# Sheet.net
KiCad netlist of a schematic drawn in Altium Designer
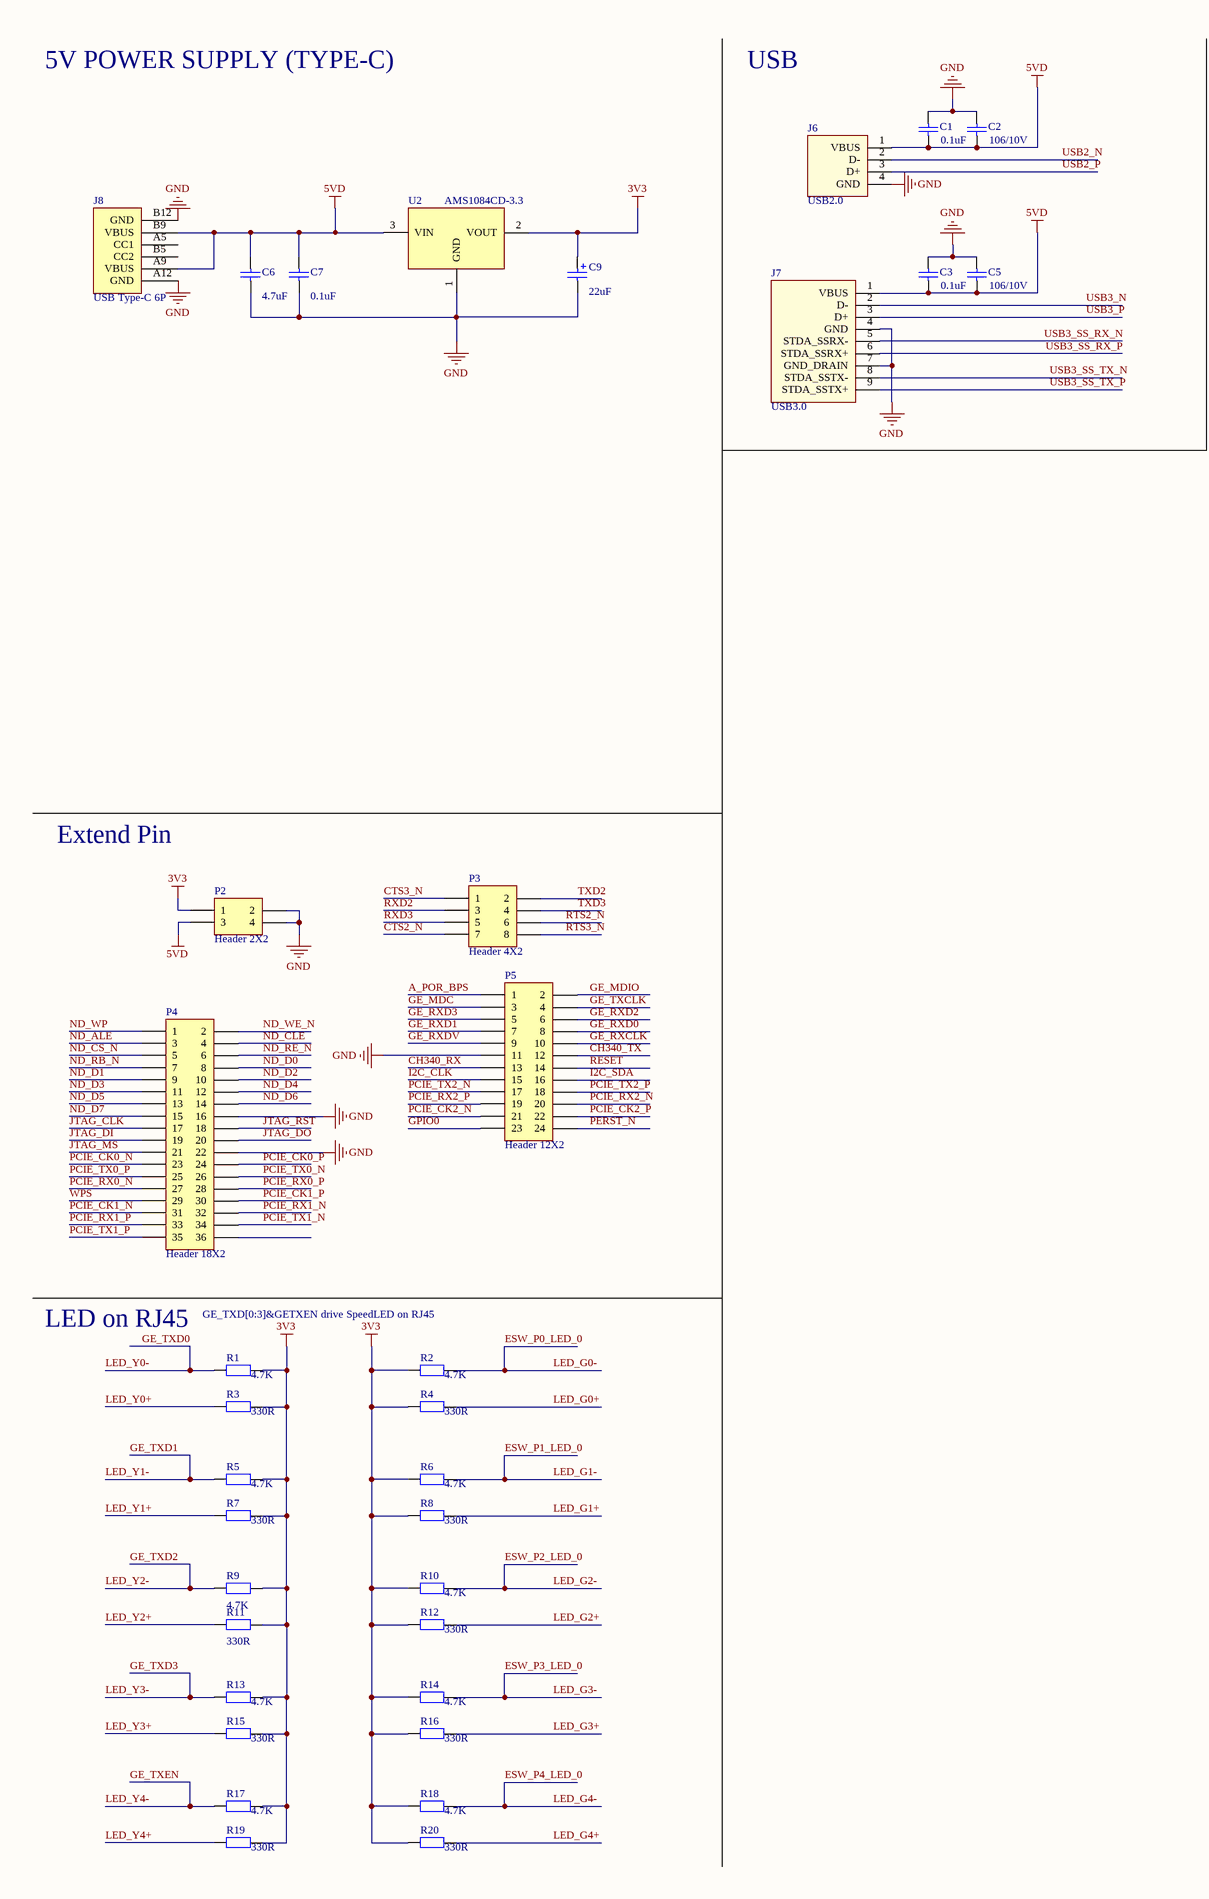
[diagram p0: Sheet.SchDoc, left]
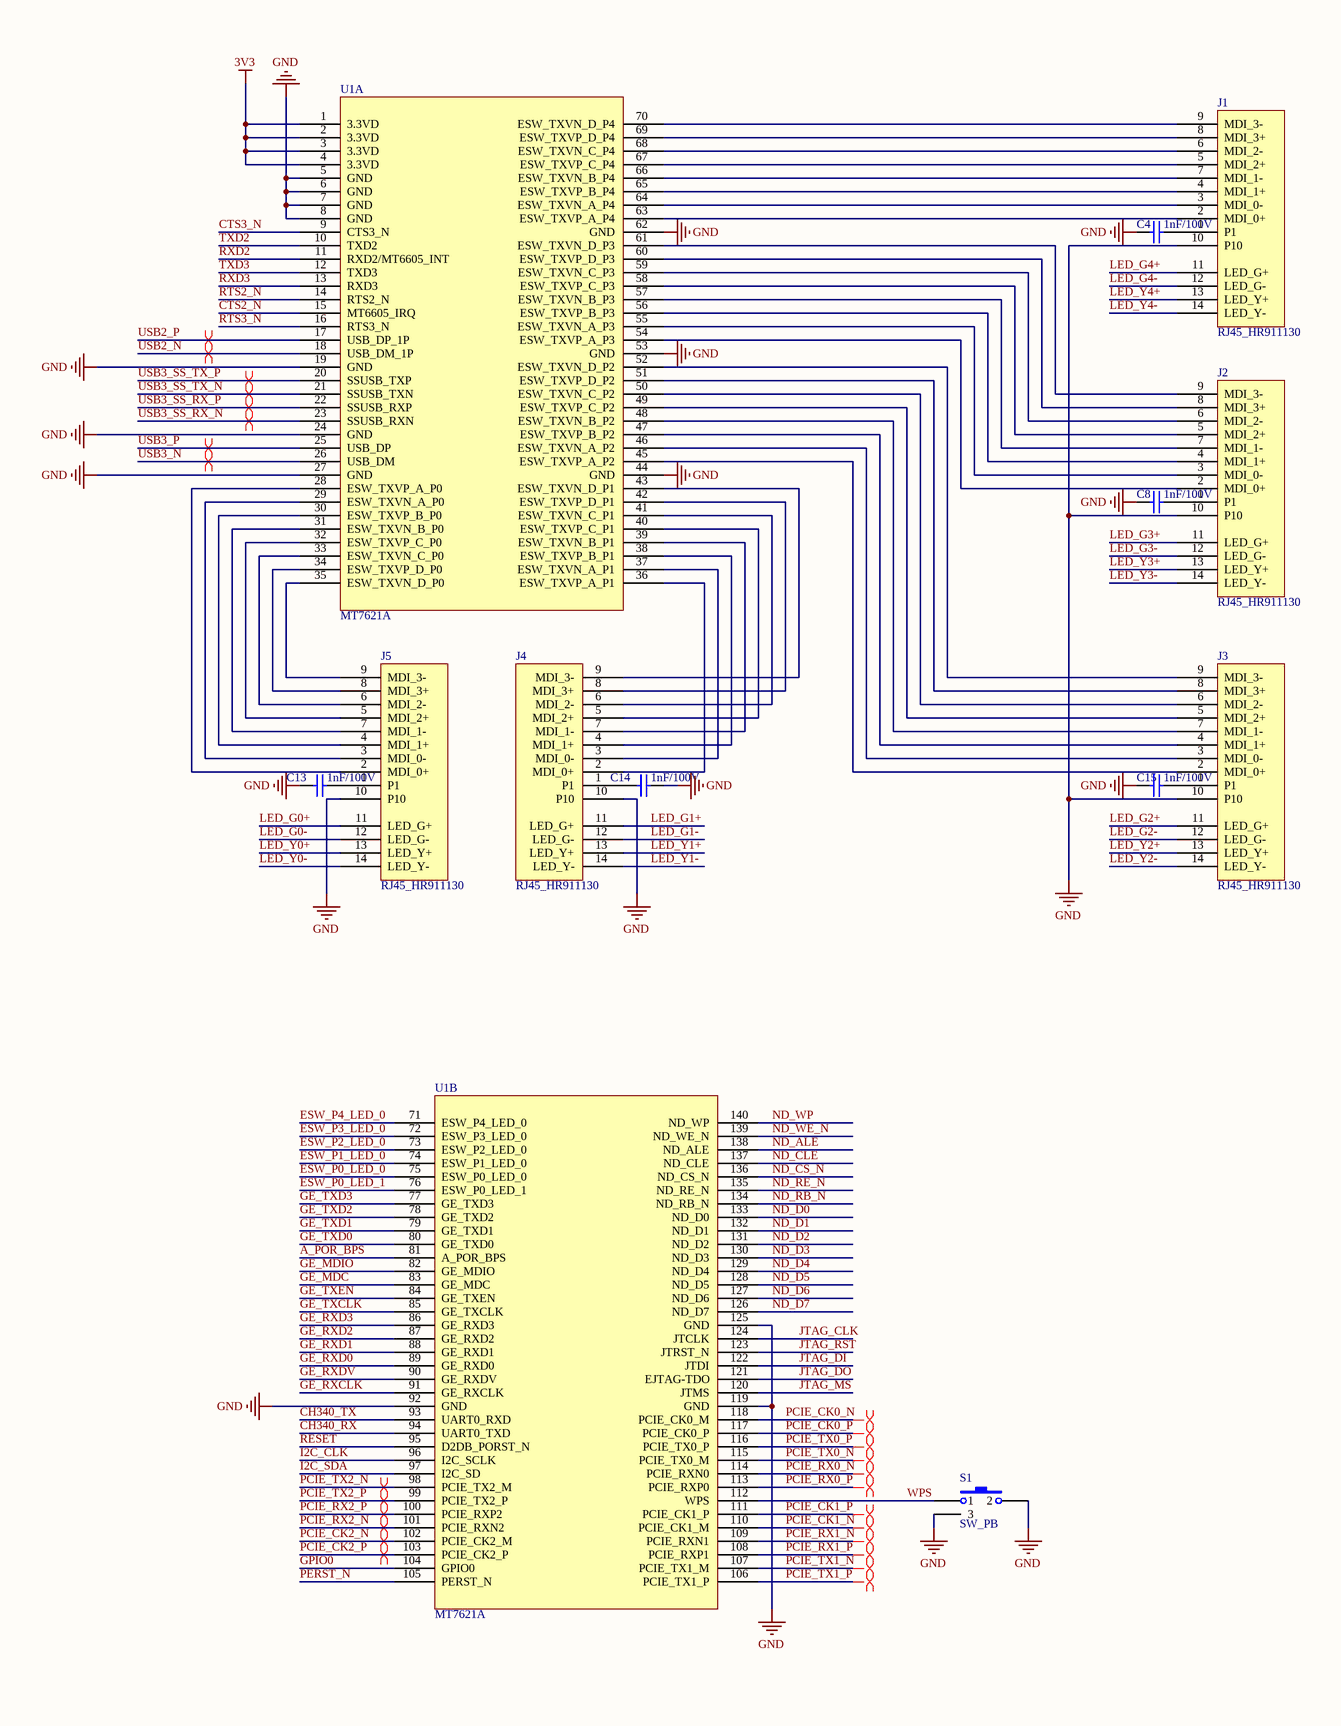
[diagram p1: Sheet.SchDoc, right]

(export (version "E")
  (design (tool "Eeschema 10.0.6"))
  (components
    (comp (ref "C1")
      (value "0.1uF")
      (footprint "6-0805")
      (description "Capacitor")
      (fields (field (name "Comment") "Cap") (field (name "PUBLISHER") "Altium Limited"))
      (libsource (lib "Miscellaneous Devices") (part "Cap"))
    )
    (comp (ref "C2")
      (value "106/10V")
      (footprint "6-0805")
      (description "Capacitor")
      (fields (field (name "Comment") "Cap") (field (name "PUBLISHER") "Altium Limited"))
      (libsource (lib "Miscellaneous Devices") (part "Cap"))
    )
    (comp (ref "C3")
      (value "0.1uF")
      (footprint "6-0805")
      (description "Capacitor")
      (fields (field (name "Comment") "Cap") (field (name "PUBLISHER") "Altium Limited"))
      (libsource (lib "Miscellaneous Devices") (part "Cap"))
    )
    (comp (ref "C4")
      (value "1nF/100V")
      (footprint "6-0805")
      (description "Capacitor")
      (fields (field (name "Comment") "Cap") (field (name "PUBLISHER") "Altium Limited"))
      (libsource (lib "Miscellaneous Devices") (part "Cap"))
    )
    (comp (ref "C5")
      (value "106/10V")
      (footprint "6-0805")
      (description "Capacitor")
      (fields (field (name "Comment") "Cap") (field (name "PUBLISHER") "Altium Limited"))
      (libsource (lib "Miscellaneous Devices") (part "Cap"))
    )
    (comp (ref "C6")
      (value "4.7uF")
      (footprint "6-0805")
      (description "Capacitor")
      (fields (field (name "Comment") "Cap") (field (name "PUBLISHER") "Altium Limited"))
      (libsource (lib "Miscellaneous Devices") (part "Cap"))
    )
    (comp (ref "C7")
      (value "0.1uF")
      (footprint "6-0805")
      (description "Capacitor")
      (fields (field (name "Comment") "Cap") (field (name "PUBLISHER") "Altium Limited"))
      (libsource (lib "Miscellaneous Devices") (part "Cap"))
    )
    (comp (ref "C8")
      (value "1nF/100V")
      (footprint "6-0805")
      (description "Capacitor")
      (fields (field (name "Comment") "Cap") (field (name "PUBLISHER") "Altium Limited"))
      (libsource (lib "Miscellaneous Devices") (part "Cap"))
    )
    (comp (ref "C9")
      (value "22uF")
      (footprint "3528B")
      (description "Polarized Capacitor (Axial)")
      (fields (field (name "Comment") "Cap Pol2") (field (name "PUBLISHER") "Altium Limited"))
      (libsource (lib "Miscellaneous Devices") (part "Cap Pol2"))
    )
    (comp (ref "C13")
      (value "1nF/100V")
      (footprint "6-0805")
      (description "Capacitor")
      (fields (field (name "Comment") "Cap") (field (name "PUBLISHER") "Altium Limited"))
      (libsource (lib "Miscellaneous Devices") (part "Cap"))
    )
    (comp (ref "C14")
      (value "1nF/100V")
      (footprint "6-0805")
      (description "Capacitor")
      (fields (field (name "Comment") "Cap") (field (name "PUBLISHER") "Altium Limited"))
      (libsource (lib "Miscellaneous Devices") (part "Cap"))
    )
    (comp (ref "C15")
      (value "1nF/100V")
      (footprint "6-0805")
      (description "Capacitor")
      (fields (field (name "Comment") "Cap") (field (name "PUBLISHER") "Altium Limited"))
      (libsource (lib "Miscellaneous Devices") (part "Cap"))
    )
    (comp (ref "J1")
      (value "RJ45_HR911130")
      (footprint "RJ45_HR911130")
      (libsource (lib "7621_cmp") (part "RJ45_HR911130"))
    )
    (comp (ref "J2")
      (value "RJ45_HR911130")
      (footprint "RJ45_HR911130")
      (libsource (lib "7621_cmp") (part "RJ45_HR911130"))
    )
    (comp (ref "J3")
      (value "RJ45_HR911130")
      (footprint "RJ45_HR911130")
      (libsource (lib "7621_cmp") (part "RJ45_HR911130"))
    )
    (comp (ref "J4")
      (value "RJ45_HR911130")
      (footprint "RJ45_HR911130")
      (libsource (lib "") (part "RJ45_HR911130_1"))
    )
    (comp (ref "J5")
      (value "RJ45_HR911130")
      (footprint "RJ45_HR911130")
      (libsource (lib "7621_cmp") (part "RJ45_HR911130"))
    )
    (comp (ref "J6") (value "USB2.0") (footprint "USB2.0") (libsource (lib "7621_cmp") (part "USB2.0")))
    (comp (ref "J7") (value "USB3.0") (footprint "USB3.0_0") (libsource (lib "7621_cmp") (part "USB3.0")))
    (comp (ref "J8")
      (value "USB Type-C 6P")
      (footprint "USB Type-C 6P")
      (libsource (lib "7621_cmp") (part "USB Type-C 6P"))
    )
    (comp (ref "P2")
      (value "Header 2X2")
      (footprint "HDR2X2")
      (description "Header, 2-Pin, Dual row")
      (fields (field (name "PUBLISHER") "Altium Limited"))
      (libsource (lib "Miscellaneous Connectors") (part "Header 2X2"))
    )
    (comp (ref "P3")
      (value "Header 4X2")
      (footprint "HDR2X4")
      (description "Header, 4-Pin, Dual row")
      (fields (field (name "PUBLISHER") "Altium Limited"))
      (libsource (lib "Miscellaneous Connectors") (part "Header 4X2"))
    )
    (comp (ref "P4")
      (value "Header 18X2")
      (footprint "HDR2X18")
      (description "Header, 18-Pin, Dual row")
      (fields (field (name "PUBLISHER") "Altium Limited"))
      (libsource (lib "Miscellaneous Connectors") (part "Header 18X2"))
    )
    (comp (ref "P5")
      (value "Header 12X2")
      (footprint "HDR2X12")
      (description "Header, 12-Pin, Dual row")
      (fields (field (name "PUBLISHER") "Altium Limited"))
      (libsource (lib "Miscellaneous Connectors") (part "Header 12X2"))
    )
    (comp (ref "R1")
      (value "4.7K")
      (footprint "6-0805")
      (description "Resistor")
      (fields (field (name "Comment") "Res2") (field (name "PUBLISHER") "Altium Limited"))
      (libsource (lib "Miscellaneous Devices") (part "Res2"))
    )
    (comp (ref "R2")
      (value "4.7K")
      (footprint "6-0805")
      (description "Resistor")
      (fields (field (name "Comment") "Res2") (field (name "PUBLISHER") "Altium Limited"))
      (libsource (lib "Miscellaneous Devices") (part "Res2"))
    )
    (comp (ref "R3")
      (value "330R")
      (footprint "6-0805")
      (description "Resistor")
      (fields (field (name "Comment") "Res2") (field (name "PUBLISHER") "Altium Limited"))
      (libsource (lib "Miscellaneous Devices") (part "Res2"))
    )
    (comp (ref "R4")
      (value "330R")
      (footprint "6-0805")
      (description "Resistor")
      (fields (field (name "Comment") "Res2") (field (name "PUBLISHER") "Altium Limited"))
      (libsource (lib "Miscellaneous Devices") (part "Res2"))
    )
    (comp (ref "R5")
      (value "4.7K")
      (footprint "6-0805")
      (description "Resistor")
      (fields (field (name "Comment") "Res2") (field (name "PUBLISHER") "Altium Limited"))
      (libsource (lib "Miscellaneous Devices") (part "Res2"))
    )
    (comp (ref "R6")
      (value "4.7K")
      (footprint "6-0805")
      (description "Resistor")
      (fields (field (name "Comment") "Res2") (field (name "PUBLISHER") "Altium Limited"))
      (libsource (lib "Miscellaneous Devices") (part "Res2"))
    )
    (comp (ref "R7")
      (value "330R")
      (footprint "6-0805")
      (description "Resistor")
      (fields (field (name "Comment") "Res2") (field (name "PUBLISHER") "Altium Limited"))
      (libsource (lib "Miscellaneous Devices") (part "Res2"))
    )
    (comp (ref "R8")
      (value "330R")
      (footprint "6-0805")
      (description "Resistor")
      (fields (field (name "Comment") "Res2") (field (name "PUBLISHER") "Altium Limited"))
      (libsource (lib "Miscellaneous Devices") (part "Res2"))
    )
    (comp (ref "R9")
      (value "4.7K")
      (footprint "6-0805")
      (description "Resistor")
      (fields (field (name "Comment") "Res2") (field (name "PUBLISHER") "Altium Limited"))
      (libsource (lib "Miscellaneous Devices") (part "Res2"))
    )
    (comp (ref "R10")
      (value "4.7K")
      (footprint "6-0805")
      (description "Resistor")
      (fields (field (name "Comment") "Res2") (field (name "PUBLISHER") "Altium Limited"))
      (libsource (lib "Miscellaneous Devices") (part "Res2"))
    )
    (comp (ref "R11")
      (value "330R")
      (footprint "6-0805")
      (description "Resistor")
      (fields (field (name "Comment") "Res2") (field (name "PUBLISHER") "Altium Limited"))
      (libsource (lib "Miscellaneous Devices") (part "Res2"))
    )
    (comp (ref "R12")
      (value "330R")
      (footprint "6-0805")
      (description "Resistor")
      (fields (field (name "Comment") "Res2") (field (name "PUBLISHER") "Altium Limited"))
      (libsource (lib "Miscellaneous Devices") (part "Res2"))
    )
    (comp (ref "R13")
      (value "4.7K")
      (footprint "6-0805")
      (description "Resistor")
      (fields (field (name "Comment") "Res2") (field (name "PUBLISHER") "Altium Limited"))
      (libsource (lib "Miscellaneous Devices") (part "Res2"))
    )
    (comp (ref "R14")
      (value "4.7K")
      (footprint "6-0805")
      (description "Resistor")
      (fields (field (name "Comment") "Res2") (field (name "PUBLISHER") "Altium Limited"))
      (libsource (lib "Miscellaneous Devices") (part "Res2"))
    )
    (comp (ref "R15")
      (value "330R")
      (footprint "6-0805")
      (description "Resistor")
      (fields (field (name "Comment") "Res2") (field (name "PUBLISHER") "Altium Limited"))
      (libsource (lib "Miscellaneous Devices") (part "Res2"))
    )
    (comp (ref "R16")
      (value "330R")
      (footprint "6-0805")
      (description "Resistor")
      (fields (field (name "Comment") "Res2") (field (name "PUBLISHER") "Altium Limited"))
      (libsource (lib "Miscellaneous Devices") (part "Res2"))
    )
    (comp (ref "R17")
      (value "4.7K")
      (footprint "6-0805")
      (description "Resistor")
      (fields (field (name "Comment") "Res2") (field (name "PUBLISHER") "Altium Limited"))
      (libsource (lib "Miscellaneous Devices") (part "Res2"))
    )
    (comp (ref "R18")
      (value "4.7K")
      (footprint "6-0805")
      (description "Resistor")
      (fields (field (name "Comment") "Res2") (field (name "PUBLISHER") "Altium Limited"))
      (libsource (lib "Miscellaneous Devices") (part "Res2"))
    )
    (comp (ref "R19")
      (value "330R")
      (footprint "6-0805")
      (description "Resistor")
      (fields (field (name "Comment") "Res2") (field (name "PUBLISHER") "Altium Limited"))
      (libsource (lib "Miscellaneous Devices") (part "Res2"))
    )
    (comp (ref "R20")
      (value "330R")
      (footprint "6-0805")
      (description "Resistor")
      (fields (field (name "Comment") "Res2") (field (name "PUBLISHER") "Altium Limited"))
      (libsource (lib "Miscellaneous Devices") (part "Res2"))
    )
    (comp (ref "S1") (value "SW_PB") (footprint "SW_PB") (libsource (lib "7621_cmp") (part "SW_PB")))
    (comp (ref "U1") (value "MT7621A") (footprint "HLK-7621") (libsource (lib "7621_cmp") (part "MT7621A")))
    (comp (ref "U2")
      (value "AMS1084CD-3.3")
      (footprint "TO252")
      (libsource (lib "7621_cmp") (part "AMS1084CD-3.3"))
    )
  )
  (nets
    (net (code "1") (name "/A_POR_BPS") (class "Default")
      (node (ref "P5") (pin "1") (pinfunction "1_1") (pintype "passive"))
      (node (ref "U1") (pin "81") (pinfunction "A_POR_BPS_81") (pintype "passive"))
    )
    (net (code "2") (name "/CH340_RX") (class "Default")
      (node (ref "P5") (pin "13") (pinfunction "13_13") (pintype "passive"))
      (node (ref "U1") (pin "94") (pinfunction "UART0_TXD_94") (pintype "passive"))
    )
    (net (code "3") (name "/CH340_TX") (class "Default")
      (node (ref "P5") (pin "12") (pinfunction "12_12") (pintype "passive"))
      (node (ref "U1") (pin "93") (pinfunction "UART0_RXD_93") (pintype "passive"))
    )
    (net (code "4") (name "/CTS2_N") (class "Default")
      (node (ref "P3") (pin "7") (pinfunction "7_7") (pintype "passive"))
      (node (ref "U1") (pin "15") (pinfunction "MT6605_IRQ_15") (pintype "passive"))
    )
    (net (code "5") (name "/CTS3_N") (class "Default")
      (node (ref "P3") (pin "1") (pinfunction "1_1") (pintype "passive"))
      (node (ref "U1") (pin "9") (pinfunction "CTS3_N_9") (pintype "passive"))
    )
    (net (code "6") (name "/ESW_P0_LED_0") (class "Default")
      (node (ref "J5") (pin "12") (pinfunction "LED_G-_12") (pintype "passive"))
      (node (ref "R2") (pin "2") (pinfunction "2_2") (pintype "passive"))
      (node (ref "U1") (pin "75") (pinfunction "ESW_P0_LED_0_75") (pintype "passive"))
    )
    (net (code "7") (name "/ESW_P0_LED_1") (class "Default")
      (node (ref "U1") (pin "76") (pinfunction "ESW_P0_LED_1_76") (pintype "passive"))
    )
    (net (code "8") (name "/ESW_P1_LED_0") (class "Default")
      (node (ref "J4") (pin "12") (pinfunction "LED_G-_12") (pintype "passive"))
      (node (ref "R6") (pin "2") (pinfunction "2_2") (pintype "passive"))
      (node (ref "U1") (pin "74") (pinfunction "ESW_P1_LED_0_74") (pintype "passive"))
    )
    (net (code "9") (name "/ESW_P2_LED_0") (class "Default")
      (node (ref "J3") (pin "12") (pinfunction "LED_G-_12") (pintype "passive"))
      (node (ref "R10") (pin "2") (pinfunction "2_2") (pintype "passive"))
      (node (ref "U1") (pin "73") (pinfunction "ESW_P2_LED_0_73") (pintype "passive"))
    )
    (net (code "10") (name "/ESW_P3_LED_0") (class "Default")
      (node (ref "J2") (pin "12") (pinfunction "LED_G-_12") (pintype "passive"))
      (node (ref "R14") (pin "2") (pinfunction "2_2") (pintype "passive"))
      (node (ref "U1") (pin "72") (pinfunction "ESW_P3_LED_0_72") (pintype "passive"))
    )
    (net (code "11") (name "/ESW_P4_LED_0") (class "Default")
      (node (ref "J1") (pin "12") (pinfunction "LED_G-_12") (pintype "passive"))
      (node (ref "R18") (pin "2") (pinfunction "2_2") (pintype "passive"))
      (node (ref "U1") (pin "71") (pinfunction "ESW_P4_LED_0_71") (pintype "passive"))
    )
    (net (code "12") (name "/GE_MDC") (class "Default")
      (node (ref "P5") (pin "3") (pinfunction "3_3") (pintype "passive"))
      (node (ref "U1") (pin "83") (pinfunction "GE_MDC_83") (pintype "passive"))
    )
    (net (code "13") (name "/GE_MDIO") (class "Default")
      (node (ref "P5") (pin "2") (pinfunction "2_2") (pintype "passive"))
      (node (ref "U1") (pin "82") (pinfunction "GE_MDIO_82") (pintype "passive"))
    )
    (net (code "14") (name "/GE_RXCLK") (class "Default")
      (node (ref "P5") (pin "10") (pinfunction "10_10") (pintype "passive"))
      (node (ref "U1") (pin "91") (pinfunction "GE_RXCLK_91") (pintype "passive"))
    )
    (net (code "15") (name "/GE_RXD0") (class "Default")
      (node (ref "P5") (pin "8") (pinfunction "8_8") (pintype "passive"))
      (node (ref "U1") (pin "89") (pinfunction "GE_RXD0_89") (pintype "passive"))
    )
    (net (code "16") (name "/GE_RXD1") (class "Default")
      (node (ref "P5") (pin "7") (pinfunction "7_7") (pintype "passive"))
      (node (ref "U1") (pin "88") (pinfunction "GE_RXD1_88") (pintype "passive"))
    )
    (net (code "17") (name "/GE_RXD2") (class "Default")
      (node (ref "P5") (pin "6") (pinfunction "6_6") (pintype "passive"))
      (node (ref "U1") (pin "87") (pinfunction "GE_RXD2_87") (pintype "passive"))
    )
    (net (code "18") (name "/GE_RXD3") (class "Default")
      (node (ref "P5") (pin "5") (pinfunction "5_5") (pintype "passive"))
      (node (ref "U1") (pin "86") (pinfunction "GE_RXD3_86") (pintype "passive"))
    )
    (net (code "19") (name "/GE_RXDV") (class "Default")
      (node (ref "P5") (pin "9") (pinfunction "9_9") (pintype "passive"))
      (node (ref "U1") (pin "90") (pinfunction "GE_RXDV_90") (pintype "passive"))
    )
    (net (code "20") (name "/GE_TXCLK") (class "Default")
      (node (ref "P5") (pin "4") (pinfunction "4_4") (pintype "passive"))
      (node (ref "U1") (pin "85") (pinfunction "GE_TXCLK_85") (pintype "passive"))
    )
    (net (code "21") (name "/GE_TXD0") (class "Default")
      (node (ref "J5") (pin "14") (pinfunction "LED_Y-_14") (pintype "passive"))
      (node (ref "R1") (pin "1") (pinfunction "1_1") (pintype "passive"))
      (node (ref "U1") (pin "80") (pinfunction "GE_TXD0_80") (pintype "passive"))
    )
    (net (code "22") (name "/GE_TXD1") (class "Default")
      (node (ref "J4") (pin "14") (pinfunction "LED_Y-_14") (pintype "passive"))
      (node (ref "R5") (pin "1") (pinfunction "1_1") (pintype "passive"))
      (node (ref "U1") (pin "79") (pinfunction "GE_TXD1_79") (pintype "passive"))
    )
    (net (code "23") (name "/GE_TXD2") (class "Default")
      (node (ref "J3") (pin "14") (pinfunction "LED_Y-_14") (pintype "passive"))
      (node (ref "R9") (pin "1") (pinfunction "1_1") (pintype "passive"))
      (node (ref "U1") (pin "78") (pinfunction "GE_TXD2_78") (pintype "passive"))
    )
    (net (code "24") (name "/GE_TXD3") (class "Default")
      (node (ref "J2") (pin "14") (pinfunction "LED_Y-_14") (pintype "passive"))
      (node (ref "R13") (pin "1") (pinfunction "1_1") (pintype "passive"))
      (node (ref "U1") (pin "77") (pinfunction "GE_TXD3_77") (pintype "passive"))
    )
    (net (code "25") (name "/GE_TXEN") (class "Default")
      (node (ref "J1") (pin "14") (pinfunction "LED_Y-_14") (pintype "passive"))
      (node (ref "R17") (pin "1") (pinfunction "1_1") (pintype "passive"))
      (node (ref "U1") (pin "84") (pinfunction "GE_TXEN_84") (pintype "passive"))
    )
    (net (code "26") (name "/GPIO0") (class "Default")
      (node (ref "P5") (pin "23") (pinfunction "23_23") (pintype "passive"))
      (node (ref "U1") (pin "104") (pinfunction "GPIO0_104") (pintype "passive"))
    )
    (net (code "27") (name "/I2C_CLK") (class "Default")
      (node (ref "P5") (pin "15") (pinfunction "15_15") (pintype "passive"))
      (node (ref "U1") (pin "96") (pinfunction "I2C_SCLK_96") (pintype "passive"))
    )
    (net (code "28") (name "/I2C_SDA") (class "Default")
      (node (ref "P5") (pin "16") (pinfunction "16_16") (pintype "passive"))
      (node (ref "U1") (pin "97") (pinfunction "I2C_SD_97") (pintype "passive"))
    )
    (net (code "29") (name "/JTAG_CLK") (class "Default")
      (node (ref "P4") (pin "17") (pinfunction "17_17") (pintype "passive"))
      (node (ref "U1") (pin "124") (pinfunction "JTCLK_124") (pintype "passive"))
    )
    (net (code "30") (name "/JTAG_DI") (class "Default")
      (node (ref "P4") (pin "19") (pinfunction "19_19") (pintype "passive"))
      (node (ref "U1") (pin "122") (pinfunction "JTDI_122") (pintype "passive"))
    )
    (net (code "31") (name "/JTAG_DO") (class "Default")
      (node (ref "P4") (pin "20") (pinfunction "20_20") (pintype "passive"))
      (node (ref "U1") (pin "121") (pinfunction "EJTAG-TDO_121") (pintype "passive"))
    )
    (net (code "32") (name "/JTAG_MS") (class "Default")
      (node (ref "P4") (pin "21") (pinfunction "21_21") (pintype "passive"))
      (node (ref "U1") (pin "120") (pinfunction "JTMS_120") (pintype "passive"))
    )
    (net (code "33") (name "/JTAG_RST") (class "Default")
      (node (ref "P4") (pin "18") (pinfunction "18_18") (pintype "passive"))
      (node (ref "U1") (pin "123") (pinfunction "JTRST_N_123") (pintype "passive"))
    )
    (net (code "34") (name "/LED_G0+") (class "Default")
      (node (ref "J5") (pin "11") (pinfunction "LED_G+_11") (pintype "passive"))
      (node (ref "R4") (pin "2") (pinfunction "2_2") (pintype "passive"))
    )
    (net (code "35") (name "/LED_G1+") (class "Default")
      (node (ref "J4") (pin "11") (pinfunction "LED_G+_11") (pintype "passive"))
      (node (ref "R8") (pin "2") (pinfunction "2_2") (pintype "passive"))
    )
    (net (code "36") (name "/LED_G2+") (class "Default")
      (node (ref "J3") (pin "11") (pinfunction "LED_G+_11") (pintype "passive"))
      (node (ref "R12") (pin "2") (pinfunction "2_2") (pintype "passive"))
    )
    (net (code "37") (name "/LED_G3+") (class "Default")
      (node (ref "J2") (pin "11") (pinfunction "LED_G+_11") (pintype "passive"))
      (node (ref "R16") (pin "2") (pinfunction "2_2") (pintype "passive"))
    )
    (net (code "38") (name "/LED_G4+") (class "Default")
      (node (ref "J1") (pin "11") (pinfunction "LED_G+_11") (pintype "passive"))
      (node (ref "R20") (pin "2") (pinfunction "2_2") (pintype "passive"))
    )
    (net (code "39") (name "/LED_Y0+") (class "Default")
      (node (ref "J5") (pin "13") (pinfunction "LED_Y+_13") (pintype "passive"))
      (node (ref "R3") (pin "1") (pinfunction "1_1") (pintype "passive"))
    )
    (net (code "40") (name "/LED_Y1+") (class "Default")
      (node (ref "J4") (pin "13") (pinfunction "LED_Y+_13") (pintype "passive"))
      (node (ref "R7") (pin "1") (pinfunction "1_1") (pintype "passive"))
    )
    (net (code "41") (name "/LED_Y2+") (class "Default")
      (node (ref "J3") (pin "13") (pinfunction "LED_Y+_13") (pintype "passive"))
      (node (ref "R11") (pin "1") (pinfunction "1_1") (pintype "passive"))
    )
    (net (code "42") (name "/LED_Y3+") (class "Default")
      (node (ref "J2") (pin "13") (pinfunction "LED_Y+_13") (pintype "passive"))
      (node (ref "R15") (pin "1") (pinfunction "1_1") (pintype "passive"))
    )
    (net (code "43") (name "/LED_Y4+") (class "Default")
      (node (ref "J1") (pin "13") (pinfunction "LED_Y+_13") (pintype "passive"))
      (node (ref "R19") (pin "1") (pinfunction "1_1") (pintype "passive"))
    )
    (net (code "44") (name "/ND_ALE") (class "Default")
      (node (ref "P4") (pin "3") (pinfunction "3_3") (pintype "passive"))
      (node (ref "U1") (pin "138") (pinfunction "ND_ALE_138") (pintype "passive"))
    )
    (net (code "45") (name "/ND_CLE") (class "Default")
      (node (ref "P4") (pin "4") (pinfunction "4_4") (pintype "passive"))
      (node (ref "U1") (pin "137") (pinfunction "ND_CLE_137") (pintype "passive"))
    )
    (net (code "46") (name "/ND_CS_N") (class "Default")
      (node (ref "P4") (pin "5") (pinfunction "5_5") (pintype "passive"))
      (node (ref "U1") (pin "136") (pinfunction "ND_CS_N_136") (pintype "passive"))
    )
    (net (code "47") (name "/ND_D0") (class "Default")
      (node (ref "P4") (pin "8") (pinfunction "8_8") (pintype "passive"))
      (node (ref "U1") (pin "133") (pinfunction "ND_D0_133") (pintype "passive"))
    )
    (net (code "48") (name "/ND_D1") (class "Default")
      (node (ref "P4") (pin "9") (pinfunction "9_9") (pintype "passive"))
      (node (ref "U1") (pin "132") (pinfunction "ND_D1_132") (pintype "passive"))
    )
    (net (code "49") (name "/ND_D2") (class "Default")
      (node (ref "P4") (pin "10") (pinfunction "10_10") (pintype "passive"))
      (node (ref "U1") (pin "131") (pinfunction "ND_D2_131") (pintype "passive"))
    )
    (net (code "50") (name "/ND_D3") (class "Default")
      (node (ref "P4") (pin "11") (pinfunction "11_11") (pintype "passive"))
      (node (ref "U1") (pin "130") (pinfunction "ND_D3_130") (pintype "passive"))
    )
    (net (code "51") (name "/ND_D4") (class "Default")
      (node (ref "P4") (pin "12") (pinfunction "12_12") (pintype "passive"))
      (node (ref "U1") (pin "129") (pinfunction "ND_D4_129") (pintype "passive"))
    )
    (net (code "52") (name "/ND_D5") (class "Default")
      (node (ref "P4") (pin "13") (pinfunction "13_13") (pintype "passive"))
      (node (ref "U1") (pin "128") (pinfunction "ND_D5_128") (pintype "passive"))
    )
    (net (code "53") (name "/ND_D6") (class "Default")
      (node (ref "P4") (pin "14") (pinfunction "14_14") (pintype "passive"))
      (node (ref "U1") (pin "127") (pinfunction "ND_D6_127") (pintype "passive"))
    )
    (net (code "54") (name "/ND_D7") (class "Default")
      (node (ref "P4") (pin "15") (pinfunction "15_15") (pintype "passive"))
      (node (ref "U1") (pin "126") (pinfunction "ND_D7_126") (pintype "passive"))
    )
    (net (code "55") (name "/ND_RB_N") (class "Default")
      (node (ref "P4") (pin "7") (pinfunction "7_7") (pintype "passive"))
      (node (ref "U1") (pin "134") (pinfunction "ND_RB_N_134") (pintype "passive"))
    )
    (net (code "56") (name "/ND_RE_N") (class "Default")
      (node (ref "P4") (pin "6") (pinfunction "6_6") (pintype "passive"))
      (node (ref "U1") (pin "135") (pinfunction "ND_RE_N_135") (pintype "passive"))
    )
    (net (code "57") (name "/ND_WE_N") (class "Default")
      (node (ref "P4") (pin "2") (pinfunction "2_2") (pintype "passive"))
      (node (ref "U1") (pin "139") (pinfunction "ND_WE_N_139") (pintype "passive"))
    )
    (net (code "58") (name "/ND_WP") (class "Default")
      (node (ref "P4") (pin "1") (pinfunction "1_1") (pintype "passive"))
      (node (ref "U1") (pin "140") (pinfunction "ND_WP_140") (pintype "passive"))
    )
    (net (code "59") (name "/PCIE_CK0_N") (class "Default")
      (node (ref "P4") (pin "23") (pinfunction "23_23") (pintype "passive"))
      (node (ref "U1") (pin "118") (pinfunction "PCIE_CK0_M_118") (pintype "passive"))
    )
    (net (code "60") (name "/PCIE_CK0_P") (class "Default")
      (node (ref "P4") (pin "24") (pinfunction "24_24") (pintype "passive"))
      (node (ref "U1") (pin "117") (pinfunction "PCIE_CK0_P_117") (pintype "passive"))
    )
    (net (code "61") (name "/PCIE_CK1_N") (class "Default")
      (node (ref "P4") (pin "31") (pinfunction "31_31") (pintype "passive"))
      (node (ref "U1") (pin "110") (pinfunction "PCIE_CK1_M_110") (pintype "passive"))
    )
    (net (code "62") (name "/PCIE_CK1_P") (class "Default")
      (node (ref "P4") (pin "30") (pinfunction "30_30") (pintype "passive"))
      (node (ref "U1") (pin "111") (pinfunction "PCIE_CK1_P_111") (pintype "passive"))
    )
    (net (code "63") (name "/PCIE_CK2_N") (class "Default")
      (node (ref "P5") (pin "21") (pinfunction "21_21") (pintype "passive"))
      (node (ref "U1") (pin "102") (pinfunction "PCIE_CK2_M_102") (pintype "passive"))
    )
    (net (code "64") (name "/PCIE_CK2_P") (class "Default")
      (node (ref "P5") (pin "22") (pinfunction "22_22") (pintype "passive"))
      (node (ref "U1") (pin "103") (pinfunction "PCIE_CK2_P_103") (pintype "passive"))
    )
    (net (code "65") (name "/PCIE_RX0_N") (class "Default")
      (node (ref "P4") (pin "27") (pinfunction "27_27") (pintype "passive"))
      (node (ref "U1") (pin "114") (pinfunction "PCIE_RXN0_114") (pintype "passive"))
    )
    (net (code "66") (name "/PCIE_RX0_P") (class "Default")
      (node (ref "P4") (pin "28") (pinfunction "28_28") (pintype "passive"))
      (node (ref "U1") (pin "113") (pinfunction "PCIE_RXP0_113") (pintype "passive"))
    )
    (net (code "67") (name "/PCIE_RX1_N") (class "Default")
      (node (ref "P4") (pin "32") (pinfunction "32_32") (pintype "passive"))
      (node (ref "U1") (pin "109") (pinfunction "PCIE_RXN1_109") (pintype "passive"))
    )
    (net (code "68") (name "/PCIE_RX1_P") (class "Default")
      (node (ref "P4") (pin "33") (pinfunction "33_33") (pintype "passive"))
      (node (ref "U1") (pin "108") (pinfunction "PCIE_RXP1_108") (pintype "passive"))
    )
    (net (code "69") (name "/PCIE_RX2_N") (class "Default")
      (node (ref "P5") (pin "20") (pinfunction "20_20") (pintype "passive"))
      (node (ref "U1") (pin "101") (pinfunction "PCIE_RXN2_101") (pintype "passive"))
    )
    (net (code "70") (name "/PCIE_RX2_P") (class "Default")
      (node (ref "P5") (pin "19") (pinfunction "19_19") (pintype "passive"))
      (node (ref "U1") (pin "100") (pinfunction "PCIE_RXP2_100") (pintype "passive"))
    )
    (net (code "71") (name "/PCIE_TX0_N") (class "Default")
      (node (ref "P4") (pin "26") (pinfunction "26_26") (pintype "passive"))
      (node (ref "U1") (pin "115") (pinfunction "PCIE_TX0_M_115") (pintype "passive"))
    )
    (net (code "72") (name "/PCIE_TX0_P") (class "Default")
      (node (ref "P4") (pin "25") (pinfunction "25_25") (pintype "passive"))
      (node (ref "U1") (pin "116") (pinfunction "PCIE_TX0_P_116") (pintype "passive"))
    )
    (net (code "73") (name "/PCIE_TX1_N") (class "Default")
      (node (ref "P4") (pin "34") (pinfunction "34_34") (pintype "passive"))
      (node (ref "U1") (pin "107") (pinfunction "PCIE_TX1_M_107") (pintype "passive"))
    )
    (net (code "74") (name "/PCIE_TX1_P") (class "Default")
      (node (ref "P4") (pin "35") (pinfunction "35_35") (pintype "passive"))
      (node (ref "U1") (pin "106") (pinfunction "PCIE_TX1_P_106") (pintype "passive"))
    )
    (net (code "75") (name "/PCIE_TX2_N") (class "Default")
      (node (ref "P5") (pin "17") (pinfunction "17_17") (pintype "passive"))
      (node (ref "U1") (pin "98") (pinfunction "PCIE_TX2_M_98") (pintype "passive"))
    )
    (net (code "76") (name "/PCIE_TX2_P") (class "Default")
      (node (ref "P5") (pin "18") (pinfunction "18_18") (pintype "passive"))
      (node (ref "U1") (pin "99") (pinfunction "PCIE_TX2_P_99") (pintype "passive"))
    )
    (net (code "77") (name "/PERST_N") (class "Default")
      (node (ref "P5") (pin "24") (pinfunction "24_24") (pintype "passive"))
      (node (ref "U1") (pin "105") (pinfunction "PERST_N_105") (pintype "passive"))
    )
    (net (code "78") (name "/RESET") (class "Default")
      (node (ref "P5") (pin "14") (pinfunction "14_14") (pintype "passive"))
      (node (ref "U1") (pin "95") (pinfunction "D2DB_PORST_N_95") (pintype "passive"))
    )
    (net (code "79") (name "/RTS2_N") (class "Default")
      (node (ref "P3") (pin "6") (pinfunction "6_6") (pintype "passive"))
      (node (ref "U1") (pin "14") (pinfunction "RTS2_N_14") (pintype "passive"))
    )
    (net (code "80") (name "/RTS3_N") (class "Default")
      (node (ref "P3") (pin "8") (pinfunction "8_8") (pintype "passive"))
      (node (ref "U1") (pin "16") (pinfunction "RTS3_N_16") (pintype "passive"))
    )
    (net (code "81") (name "/RXD2") (class "Default")
      (node (ref "P3") (pin "3") (pinfunction "3_3") (pintype "passive"))
      (node (ref "U1") (pin "11") (pinfunction "RXD2/MT6605_INT_11") (pintype "passive"))
    )
    (net (code "82") (name "/RXD3") (class "Default")
      (node (ref "P3") (pin "5") (pinfunction "5_5") (pintype "passive"))
      (node (ref "U1") (pin "13") (pinfunction "RXD3_13") (pintype "passive"))
    )
    (net (code "83") (name "/TXD2") (class "Default")
      (node (ref "P3") (pin "2") (pinfunction "2_2") (pintype "passive"))
      (node (ref "U1") (pin "10") (pinfunction "TXD2_10") (pintype "passive"))
    )
    (net (code "84") (name "/TXD3") (class "Default")
      (node (ref "P3") (pin "4") (pinfunction "4_4") (pintype "passive"))
      (node (ref "U1") (pin "12") (pinfunction "TXD3_12") (pintype "passive"))
    )
    (net (code "85") (name "/USB2_N") (class "Default")
      (node (ref "J6") (pin "2") (pinfunction "D-_2") (pintype "passive"))
      (node (ref "U1") (pin "18") (pinfunction "USB_DM_1P_18") (pintype "passive"))
    )
    (net (code "86") (name "/USB2_P") (class "Default")
      (node (ref "J6") (pin "3") (pinfunction "D+_3") (pintype "passive"))
      (node (ref "U1") (pin "17") (pinfunction "USB_DP_1P_17") (pintype "passive"))
    )
    (net (code "87") (name "/USB3_N") (class "Default")
      (node (ref "J7") (pin "2") (pinfunction "D-_2") (pintype "passive"))
      (node (ref "U1") (pin "26") (pinfunction "USB_DM_26") (pintype "passive"))
    )
    (net (code "88") (name "/USB3_P") (class "Default")
      (node (ref "J7") (pin "3") (pinfunction "D+_3") (pintype "passive"))
      (node (ref "U1") (pin "25") (pinfunction "USB_DP_25") (pintype "passive"))
    )
    (net (code "89") (name "/USB3_SS_RX_N") (class "Default")
      (node (ref "J7") (pin "5") (pinfunction "STDA_SSRX-_5") (pintype "passive"))
      (node (ref "U1") (pin "23") (pinfunction "SSUSB_RXN_23") (pintype "passive"))
    )
    (net (code "90") (name "/USB3_SS_RX_P") (class "Default")
      (node (ref "J7") (pin "6") (pinfunction "STDA_SSRX+_6") (pintype "passive"))
      (node (ref "U1") (pin "22") (pinfunction "SSUSB_RXP_22") (pintype "passive"))
    )
    (net (code "91") (name "/USB3_SS_TX_N") (class "Default")
      (node (ref "J7") (pin "8") (pinfunction "STDA_SSTX-_8") (pintype "passive"))
      (node (ref "U1") (pin "21") (pinfunction "SSUSB_TXN_21") (pintype "passive"))
    )
    (net (code "92") (name "/USB3_SS_TX_P") (class "Default")
      (node (ref "J7") (pin "9") (pinfunction "STDA_SSTX+_9") (pintype "passive"))
      (node (ref "U1") (pin "20") (pinfunction "SSUSB_TXP_20") (pintype "passive"))
    )
    (net (code "93") (name "/WPS") (class "Default")
      (node (ref "P4") (pin "29") (pinfunction "29_29") (pintype "passive"))
      (node (ref "S1") (pin "1") (pinfunction "1_1") (pintype "passive"))
      (node (ref "U1") (pin "112") (pinfunction "WPS_112") (pintype "passive"))
    )
    (net (code "94") (name "3V3") (class "Default")
      (node (ref "C9") (pin "1") (pinfunction "1_1") (pintype "passive"))
      (node (ref "P2") (pin "1") (pinfunction "1_1") (pintype "passive"))
      (node (ref "R1") (pin "2") (pinfunction "2_2") (pintype "passive"))
      (node (ref "R10") (pin "1") (pinfunction "1_1") (pintype "passive"))
      (node (ref "R11") (pin "2") (pinfunction "2_2") (pintype "passive"))
      (node (ref "R12") (pin "1") (pinfunction "1_1") (pintype "passive"))
      (node (ref "R13") (pin "2") (pinfunction "2_2") (pintype "passive"))
      (node (ref "R14") (pin "1") (pinfunction "1_1") (pintype "passive"))
      (node (ref "R15") (pin "2") (pinfunction "2_2") (pintype "passive"))
      (node (ref "R16") (pin "1") (pinfunction "1_1") (pintype "passive"))
      (node (ref "R17") (pin "2") (pinfunction "2_2") (pintype "passive"))
      (node (ref "R18") (pin "1") (pinfunction "1_1") (pintype "passive"))
      (node (ref "R19") (pin "2") (pinfunction "2_2") (pintype "passive"))
      (node (ref "R2") (pin "1") (pinfunction "1_1") (pintype "passive"))
      (node (ref "R20") (pin "1") (pinfunction "1_1") (pintype "passive"))
      (node (ref "R3") (pin "2") (pinfunction "2_2") (pintype "passive"))
      (node (ref "R4") (pin "1") (pinfunction "1_1") (pintype "passive"))
      (node (ref "R5") (pin "2") (pinfunction "2_2") (pintype "passive"))
      (node (ref "R6") (pin "1") (pinfunction "1_1") (pintype "passive"))
      (node (ref "R7") (pin "2") (pinfunction "2_2") (pintype "passive"))
      (node (ref "R8") (pin "1") (pinfunction "1_1") (pintype "passive"))
      (node (ref "R9") (pin "2") (pinfunction "2_2") (pintype "passive"))
      (node (ref "U1") (pin "1") (pinfunction "3.3VD_1") (pintype "passive"))
      (node (ref "U1") (pin "2") (pinfunction "3.3VD_2") (pintype "passive"))
      (node (ref "U1") (pin "3") (pinfunction "3.3VD_3") (pintype "passive"))
      (node (ref "U1") (pin "4") (pinfunction "3.3VD_4") (pintype "passive"))
      (node (ref "U2") (pin "2") (pinfunction "VOUT_2") (pintype "passive"))
    )
    (net (code "95") (name "5VD") (class "Default")
      (node (ref "C1") (pin "1") (pinfunction "1_1") (pintype "passive"))
      (node (ref "C2") (pin "1") (pinfunction "1_1") (pintype "passive"))
      (node (ref "C3") (pin "1") (pinfunction "1_1") (pintype "passive"))
      (node (ref "C5") (pin "1") (pinfunction "1_1") (pintype "passive"))
      (node (ref "C6") (pin "2") (pinfunction "2_2") (pintype "passive"))
      (node (ref "C7") (pin "2") (pinfunction "2_2") (pintype "passive"))
      (node (ref "J6") (pin "1") (pinfunction "VBUS_1") (pintype "passive"))
      (node (ref "J7") (pin "1") (pinfunction "VBUS_1") (pintype "passive"))
      (node (ref "J8") (pin "A9") (pinfunction "VBUS_A9") (pintype "passive"))
      (node (ref "J8") (pin "B9") (pinfunction "VBUS_B9") (pintype "passive"))
      (node (ref "P2") (pin "3") (pinfunction "3_3") (pintype "passive"))
      (node (ref "U2") (pin "3") (pinfunction "VIN_3") (pintype "passive"))
    )
    (net (code "96") (name "GND") (class "Default")
      (node (ref "C1") (pin "2") (pinfunction "2_2") (pintype "passive"))
      (node (ref "C13") (pin "2") (pinfunction "2_2") (pintype "passive"))
      (node (ref "C14") (pin "1") (pinfunction "1_1") (pintype "passive"))
      (node (ref "C15") (pin "2") (pinfunction "2_2") (pintype "passive"))
      (node (ref "C2") (pin "2") (pinfunction "2_2") (pintype "passive"))
      (node (ref "C3") (pin "2") (pinfunction "2_2") (pintype "passive"))
      (node (ref "C4") (pin "2") (pinfunction "2_2") (pintype "passive"))
      (node (ref "C5") (pin "2") (pinfunction "2_2") (pintype "passive"))
      (node (ref "C6") (pin "1") (pinfunction "1_1") (pintype "passive"))
      (node (ref "C7") (pin "1") (pinfunction "1_1") (pintype "passive"))
      (node (ref "C8") (pin "2") (pinfunction "2_2") (pintype "passive"))
      (node (ref "C9") (pin "2") (pinfunction "2_2") (pintype "passive"))
      (node (ref "J1") (pin "10") (pinfunction "P10_10") (pintype "passive"))
      (node (ref "J2") (pin "10") (pinfunction "P10_10") (pintype "passive"))
      (node (ref "J3") (pin "10") (pinfunction "P10_10") (pintype "passive"))
      (node (ref "J4") (pin "10") (pinfunction "P10_10") (pintype "passive"))
      (node (ref "J5") (pin "10") (pinfunction "P10_10") (pintype "passive"))
      (node (ref "J6") (pin "4") (pinfunction "GND_4") (pintype "passive"))
      (node (ref "J7") (pin "4") (pinfunction "GND_4") (pintype "passive"))
      (node (ref "J7") (pin "7") (pinfunction "GND_DRAIN_7") (pintype "passive"))
      (node (ref "J8") (pin "A12") (pinfunction "GND_A12") (pintype "passive"))
      (node (ref "J8") (pin "B12") (pinfunction "GND_B12") (pintype "passive"))
      (node (ref "P2") (pin "2") (pinfunction "2_2") (pintype "passive"))
      (node (ref "P2") (pin "4") (pinfunction "4_4") (pintype "passive"))
      (node (ref "P4") (pin "16") (pinfunction "16_16") (pintype "passive"))
      (node (ref "P4") (pin "22") (pinfunction "22_22") (pintype "passive"))
      (node (ref "P5") (pin "11") (pinfunction "11_11") (pintype "passive"))
      (node (ref "S1") (pin "2") (pinfunction "2_2") (pintype "passive"))
      (node (ref "S1") (pin "3") (pinfunction "3_3") (pintype "passive"))
      (node (ref "U1") (pin "119") (pinfunction "GND_119") (pintype "passive"))
      (node (ref "U1") (pin "125") (pinfunction "GND_125") (pintype "passive"))
      (node (ref "U1") (pin "19") (pinfunction "GND_19") (pintype "passive"))
      (node (ref "U1") (pin "24") (pinfunction "GND_24") (pintype "passive"))
      (node (ref "U1") (pin "27") (pinfunction "GND_27") (pintype "passive"))
      (node (ref "U1") (pin "44") (pinfunction "GND_44") (pintype "passive"))
      (node (ref "U1") (pin "5") (pinfunction "GND_5") (pintype "passive"))
      (node (ref "U1") (pin "53") (pinfunction "GND_53") (pintype "passive"))
      (node (ref "U1") (pin "6") (pinfunction "GND_6") (pintype "passive"))
      (node (ref "U1") (pin "62") (pinfunction "GND_62") (pintype "passive"))
      (node (ref "U1") (pin "7") (pinfunction "GND_7") (pintype "passive"))
      (node (ref "U1") (pin "8") (pinfunction "GND_8") (pintype "passive"))
      (node (ref "U1") (pin "92") (pinfunction "GND_92") (pintype "passive"))
      (node (ref "U2") (pin "1") (pinfunction "GND_1") (pintype "passive"))
    )
    (net (code "97") (name "Net-(J1-MDI_0+)") (class "Default")
      (node (ref "J1") (pin "2") (pinfunction "MDI_0+_2") (pintype "passive"))
      (node (ref "U1") (pin "63") (pinfunction "ESW_TXVP_A_P4_63") (pintype "passive"))
    )
    (net (code "98") (name "Net-(J1-MDI_0-)") (class "Default")
      (node (ref "J1") (pin "3") (pinfunction "MDI_0-_3") (pintype "passive"))
      (node (ref "U1") (pin "64") (pinfunction "ESW_TXVN_A_P4_64") (pintype "passive"))
    )
    (net (code "99") (name "Net-(J1-MDI_1+)") (class "Default")
      (node (ref "J1") (pin "4") (pinfunction "MDI_1+_4") (pintype "passive"))
      (node (ref "U1") (pin "65") (pinfunction "ESW_TXVP_B_P4_65") (pintype "passive"))
    )
    (net (code "100") (name "Net-(J1-MDI_1-)") (class "Default")
      (node (ref "J1") (pin "7") (pinfunction "MDI_1-_7") (pintype "passive"))
      (node (ref "U1") (pin "66") (pinfunction "ESW_TXVN_B_P4_66") (pintype "passive"))
    )
    (net (code "101") (name "Net-(J1-MDI_2+)") (class "Default")
      (node (ref "J1") (pin "5") (pinfunction "MDI_2+_5") (pintype "passive"))
      (node (ref "U1") (pin "67") (pinfunction "ESW_TXVP_C_P4_67") (pintype "passive"))
    )
    (net (code "102") (name "Net-(J1-MDI_2-)") (class "Default")
      (node (ref "J1") (pin "6") (pinfunction "MDI_2-_6") (pintype "passive"))
      (node (ref "U1") (pin "68") (pinfunction "ESW_TXVN_C_P4_68") (pintype "passive"))
    )
    (net (code "103") (name "Net-(J1-MDI_3+)") (class "Default")
      (node (ref "J1") (pin "8") (pinfunction "MDI_3+_8") (pintype "passive"))
      (node (ref "U1") (pin "69") (pinfunction "ESW_TXVP_D_P4_69") (pintype "passive"))
    )
    (net (code "104") (name "Net-(J1-MDI_3-)") (class "Default")
      (node (ref "J1") (pin "9") (pinfunction "MDI_3-_9") (pintype "passive"))
      (node (ref "U1") (pin "70") (pinfunction "ESW_TXVN_D_P4_70") (pintype "passive"))
    )
    (net (code "105") (name "Net-(J1-P1)") (class "Default")
      (node (ref "C4") (pin "1") (pinfunction "1_1") (pintype "passive"))
      (node (ref "J1") (pin "1") (pinfunction "P1_1") (pintype "passive"))
    )
    (net (code "106") (name "Net-(J2-MDI_0+)") (class "Default")
      (node (ref "J2") (pin "2") (pinfunction "MDI_0+_2") (pintype "passive"))
      (node (ref "U1") (pin "54") (pinfunction "ESW_TXVP_A_P3_54") (pintype "passive"))
    )
    (net (code "107") (name "Net-(J2-MDI_0-)") (class "Default")
      (node (ref "J2") (pin "3") (pinfunction "MDI_0-_3") (pintype "passive"))
      (node (ref "U1") (pin "55") (pinfunction "ESW_TXVN_A_P3_55") (pintype "passive"))
    )
    (net (code "108") (name "Net-(J2-MDI_1+)") (class "Default")
      (node (ref "J2") (pin "4") (pinfunction "MDI_1+_4") (pintype "passive"))
      (node (ref "U1") (pin "56") (pinfunction "ESW_TXVP_B_P3_56") (pintype "passive"))
    )
    (net (code "109") (name "Net-(J2-MDI_1-)") (class "Default")
      (node (ref "J2") (pin "7") (pinfunction "MDI_1-_7") (pintype "passive"))
      (node (ref "U1") (pin "57") (pinfunction "ESW_TXVN_B_P3_57") (pintype "passive"))
    )
    (net (code "110") (name "Net-(J2-MDI_2+)") (class "Default")
      (node (ref "J2") (pin "5") (pinfunction "MDI_2+_5") (pintype "passive"))
      (node (ref "U1") (pin "58") (pinfunction "ESW_TXVP_C_P3_58") (pintype "passive"))
    )
    (net (code "111") (name "Net-(J2-MDI_2-)") (class "Default")
      (node (ref "J2") (pin "6") (pinfunction "MDI_2-_6") (pintype "passive"))
      (node (ref "U1") (pin "59") (pinfunction "ESW_TXVN_C_P3_59") (pintype "passive"))
    )
    (net (code "112") (name "Net-(J2-MDI_3+)") (class "Default")
      (node (ref "J2") (pin "8") (pinfunction "MDI_3+_8") (pintype "passive"))
      (node (ref "U1") (pin "60") (pinfunction "ESW_TXVP_D_P3_60") (pintype "passive"))
    )
    (net (code "113") (name "Net-(J2-MDI_3-)") (class "Default")
      (node (ref "J2") (pin "9") (pinfunction "MDI_3-_9") (pintype "passive"))
      (node (ref "U1") (pin "61") (pinfunction "ESW_TXVN_D_P3_61") (pintype "passive"))
    )
    (net (code "114") (name "Net-(J2-P1)") (class "Default")
      (node (ref "C8") (pin "1") (pinfunction "1_1") (pintype "passive"))
      (node (ref "J2") (pin "1") (pinfunction "P1_1") (pintype "passive"))
    )
    (net (code "115") (name "Net-(J3-MDI_0+)") (class "Default")
      (node (ref "J3") (pin "2") (pinfunction "MDI_0+_2") (pintype "passive"))
      (node (ref "U1") (pin "45") (pinfunction "ESW_TXVP_A_P2_45") (pintype "passive"))
    )
    (net (code "116") (name "Net-(J3-MDI_0-)") (class "Default")
      (node (ref "J3") (pin "3") (pinfunction "MDI_0-_3") (pintype "passive"))
      (node (ref "U1") (pin "46") (pinfunction "ESW_TXVN_A_P2_46") (pintype "passive"))
    )
    (net (code "117") (name "Net-(J3-MDI_1+)") (class "Default")
      (node (ref "J3") (pin "4") (pinfunction "MDI_1+_4") (pintype "passive"))
      (node (ref "U1") (pin "47") (pinfunction "ESW_TXVP_B_P2_47") (pintype "passive"))
    )
    (net (code "118") (name "Net-(J3-MDI_1-)") (class "Default")
      (node (ref "J3") (pin "7") (pinfunction "MDI_1-_7") (pintype "passive"))
      (node (ref "U1") (pin "48") (pinfunction "ESW_TXVN_B_P2_48") (pintype "passive"))
    )
    (net (code "119") (name "Net-(J3-MDI_2+)") (class "Default")
      (node (ref "J3") (pin "5") (pinfunction "MDI_2+_5") (pintype "passive"))
      (node (ref "U1") (pin "49") (pinfunction "ESW_TXVP_C_P2_49") (pintype "passive"))
    )
    (net (code "120") (name "Net-(J3-MDI_2-)") (class "Default")
      (node (ref "J3") (pin "6") (pinfunction "MDI_2-_6") (pintype "passive"))
      (node (ref "U1") (pin "50") (pinfunction "ESW_TXVN_C_P2_50") (pintype "passive"))
    )
    (net (code "121") (name "Net-(J3-MDI_3+)") (class "Default")
      (node (ref "J3") (pin "8") (pinfunction "MDI_3+_8") (pintype "passive"))
      (node (ref "U1") (pin "51") (pinfunction "ESW_TXVP_D_P2_51") (pintype "passive"))
    )
    (net (code "122") (name "Net-(J3-MDI_3-)") (class "Default")
      (node (ref "J3") (pin "9") (pinfunction "MDI_3-_9") (pintype "passive"))
      (node (ref "U1") (pin "52") (pinfunction "ESW_TXVN_D_P2_52") (pintype "passive"))
    )
    (net (code "123") (name "Net-(J3-P1)") (class "Default")
      (node (ref "C15") (pin "1") (pinfunction "1_1") (pintype "passive"))
      (node (ref "J3") (pin "1") (pinfunction "P1_1") (pintype "passive"))
    )
    (net (code "124") (name "Net-(J4-MDI_0+)") (class "Default")
      (node (ref "J4") (pin "2") (pinfunction "MDI_0+_2") (pintype "passive"))
      (node (ref "U1") (pin "36") (pinfunction "ESW_TXVP_A_P1_36") (pintype "passive"))
    )
    (net (code "125") (name "Net-(J4-MDI_0-)") (class "Default")
      (node (ref "J4") (pin "3") (pinfunction "MDI_0-_3") (pintype "passive"))
      (node (ref "U1") (pin "37") (pinfunction "ESW_TXVN_A_P1_37") (pintype "passive"))
    )
    (net (code "126") (name "Net-(J4-MDI_1+)") (class "Default")
      (node (ref "J4") (pin "4") (pinfunction "MDI_1+_4") (pintype "passive"))
      (node (ref "U1") (pin "38") (pinfunction "ESW_TXVP_B_P1_38") (pintype "passive"))
    )
    (net (code "127") (name "Net-(J4-MDI_1-)") (class "Default")
      (node (ref "J4") (pin "7") (pinfunction "MDI_1-_7") (pintype "passive"))
      (node (ref "U1") (pin "39") (pinfunction "ESW_TXVN_B_P1_39") (pintype "passive"))
    )
    (net (code "128") (name "Net-(J4-MDI_2+)") (class "Default")
      (node (ref "J4") (pin "5") (pinfunction "MDI_2+_5") (pintype "passive"))
      (node (ref "U1") (pin "40") (pinfunction "ESW_TXVP_C_P1_40") (pintype "passive"))
    )
    (net (code "129") (name "Net-(J4-MDI_2-)") (class "Default")
      (node (ref "J4") (pin "6") (pinfunction "MDI_2-_6") (pintype "passive"))
      (node (ref "U1") (pin "41") (pinfunction "ESW_TXVN_C_P1_41") (pintype "passive"))
    )
    (net (code "130") (name "Net-(J4-MDI_3+)") (class "Default")
      (node (ref "J4") (pin "8") (pinfunction "MDI_3+_8") (pintype "passive"))
      (node (ref "U1") (pin "42") (pinfunction "ESW_TXVP_D_P1_42") (pintype "passive"))
    )
    (net (code "131") (name "Net-(J4-MDI_3-)") (class "Default")
      (node (ref "J4") (pin "9") (pinfunction "MDI_3-_9") (pintype "passive"))
      (node (ref "U1") (pin "43") (pinfunction "ESW_TXVN_D_P1_43") (pintype "passive"))
    )
    (net (code "132") (name "Net-(J4-P1)") (class "Default")
      (node (ref "C14") (pin "2") (pinfunction "2_2") (pintype "passive"))
      (node (ref "J4") (pin "1") (pinfunction "P1_1") (pintype "passive"))
    )
    (net (code "133") (name "Net-(J5-MDI_0+)") (class "Default")
      (node (ref "J5") (pin "2") (pinfunction "MDI_0+_2") (pintype "passive"))
      (node (ref "U1") (pin "28") (pinfunction "ESW_TXVP_A_P0_28") (pintype "passive"))
    )
    (net (code "134") (name "Net-(J5-MDI_0-)") (class "Default")
      (node (ref "J5") (pin "3") (pinfunction "MDI_0-_3") (pintype "passive"))
      (node (ref "U1") (pin "29") (pinfunction "ESW_TXVN_A_P0_29") (pintype "passive"))
    )
    (net (code "135") (name "Net-(J5-MDI_1+)") (class "Default")
      (node (ref "J5") (pin "4") (pinfunction "MDI_1+_4") (pintype "passive"))
      (node (ref "U1") (pin "30") (pinfunction "ESW_TXVP_B_P0_30") (pintype "passive"))
    )
    (net (code "136") (name "Net-(J5-MDI_1-)") (class "Default")
      (node (ref "J5") (pin "7") (pinfunction "MDI_1-_7") (pintype "passive"))
      (node (ref "U1") (pin "31") (pinfunction "ESW_TXVN_B_P0_31") (pintype "passive"))
    )
    (net (code "137") (name "Net-(J5-MDI_2+)") (class "Default")
      (node (ref "J5") (pin "5") (pinfunction "MDI_2+_5") (pintype "passive"))
      (node (ref "U1") (pin "32") (pinfunction "ESW_TXVP_C_P0_32") (pintype "passive"))
    )
    (net (code "138") (name "Net-(J5-MDI_2-)") (class "Default")
      (node (ref "J5") (pin "6") (pinfunction "MDI_2-_6") (pintype "passive"))
      (node (ref "U1") (pin "33") (pinfunction "ESW_TXVN_C_P0_33") (pintype "passive"))
    )
    (net (code "139") (name "Net-(J5-MDI_3+)") (class "Default")
      (node (ref "J5") (pin "8") (pinfunction "MDI_3+_8") (pintype "passive"))
      (node (ref "U1") (pin "34") (pinfunction "ESW_TXVP_D_P0_34") (pintype "passive"))
    )
    (net (code "140") (name "Net-(J5-MDI_3-)") (class "Default")
      (node (ref "J5") (pin "9") (pinfunction "MDI_3-_9") (pintype "passive"))
      (node (ref "U1") (pin "35") (pinfunction "ESW_TXVN_D_P0_35") (pintype "passive"))
    )
    (net (code "141") (name "Net-(J5-P1)") (class "Default")
      (node (ref "C13") (pin "1") (pinfunction "1_1") (pintype "passive"))
      (node (ref "J5") (pin "1") (pinfunction "P1_1") (pintype "passive"))
    )
    (net (code "142") (name "unconnected-(J8-CC1-PadA5)") (class "Default")
      (node (ref "J8") (pin "A5") (pinfunction "CC1_A5") (pintype "passive"))
    )
    (net (code "143") (name "unconnected-(J8-CC2-PadB5)") (class "Default")
      (node (ref "J8") (pin "B5") (pinfunction "CC2_B5") (pintype "passive"))
    )
    (net (code "144") (name "unconnected-(P4-Pad36)") (class "Default")
      (node (ref "P4") (pin "36") (pinfunction "36_36") (pintype "passive"))
    )
  )
)
